# pca10040_sheet4_connectors.net
KiCad netlist of a schematic drawn in Altium Designer
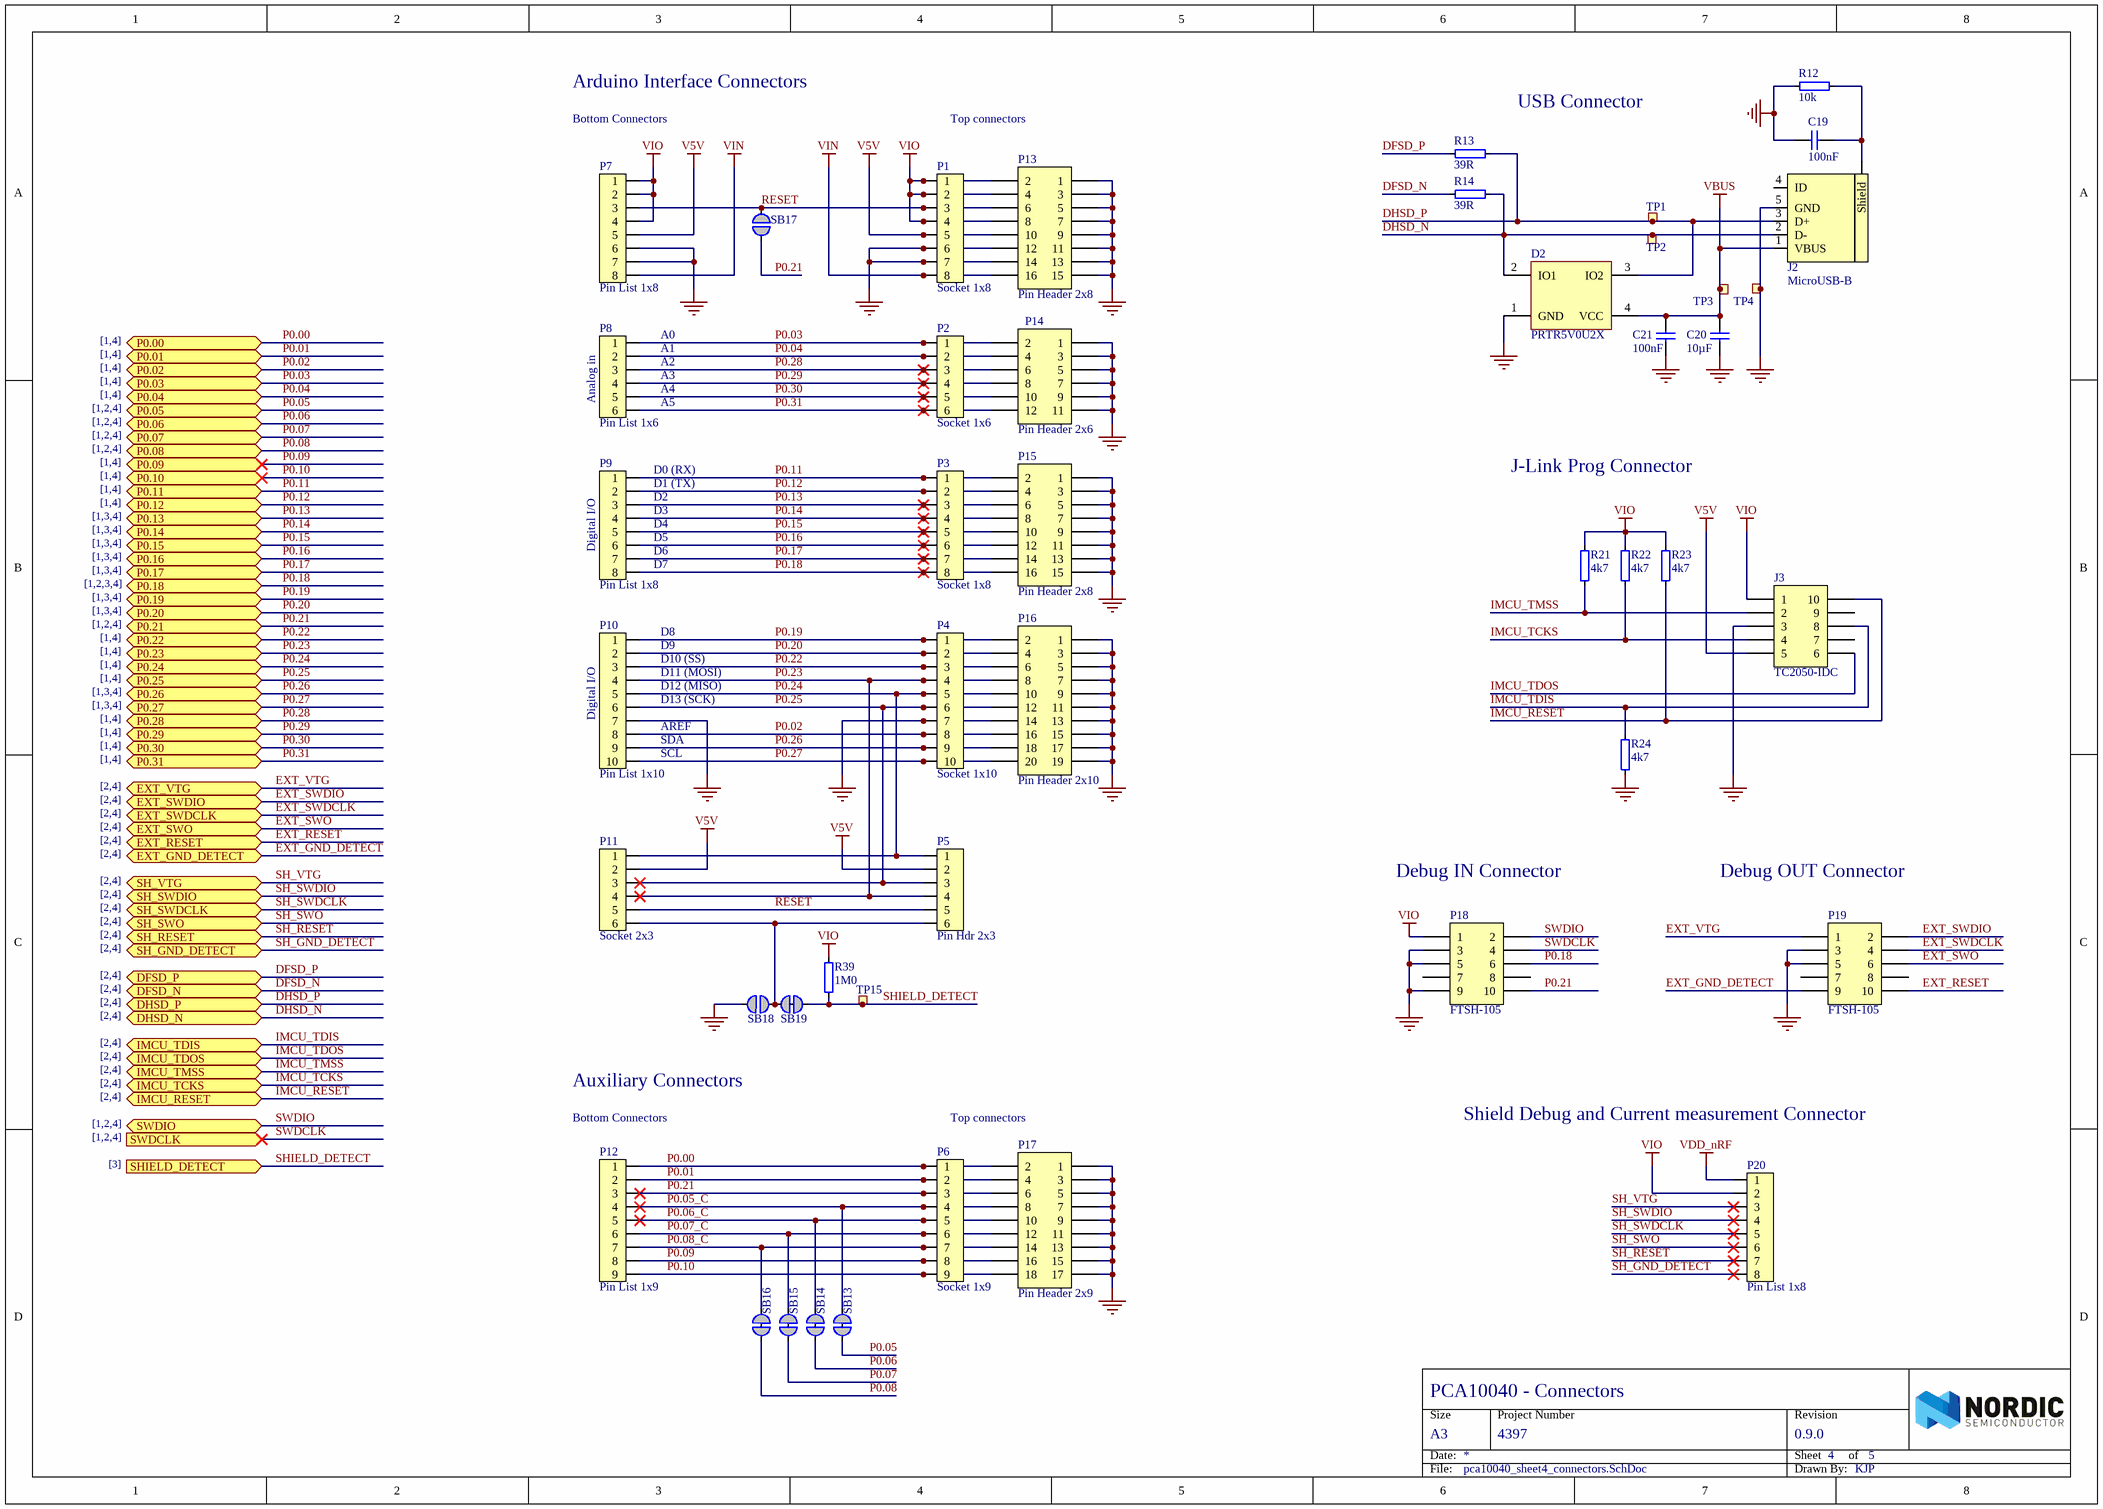
[diagram p0: pca10040_sheet4_connectors.SchDoc]

(export (version "E")
  (design (tool "Eeschema 10.0.6"))
  (components
    (comp (ref "C19")
      (value "100nF")
      (footprint "CAPC1005X04L")
      (description "Capacitor, X7R, ±10%")
      (fields (field (name "PART NUMBER") "C0402-100n") (field (name "PUBLISHER") "Nordic Semiconductor"))
      (libsource (lib "Nordic Passive DB") (part "CAP"))
    )
    (comp (ref "C20")
      (value "10µF")
      (footprint "CAPC1608X06L")
      (description "Capacitor, X5R, ±20%")
      (fields (field (name "PART NUMBER") "C0603-10µ") (field (name "PUBLISHER") "Nordic Semiconductor"))
      (libsource (lib "Nordic Passive DB") (part "CAP"))
    )
    (comp (ref "C21")
      (value "100nF")
      (footprint "CAPC1005X04L")
      (description "Capacitor, X7R, ±10%")
      (fields (field (name "PART NUMBER") "C0402-100n") (field (name "PUBLISHER") "Nordic Semiconductor"))
      (libsource (lib "Nordic Passive DB") (part "CAP"))
    )
    (comp (ref "D2")
      (value "PRTR5V0U2X")
      (footprint "SOT190P230X110-4L")
      (description "Ultra low capacitance double rail-to-rail ESD protection diode")
      (fields
        (field (name "MANUFACTURER") "NXP")
        (field (name "2ND SOURCE PART NUMBER") "152-4157")
        (field (name "PUBLISHER") "Nordic Semiconductor")
      )
      (libsource (lib "Nordic Discrete DB") (part "PRTR5V0U2X"))
    )
    (comp (ref "J2")
      (value "MicroUSB-B")
      (footprint "FCI_10118193-0001LF")
      (description "MicroUSB-B-SMT")
      (fields
        (field (name "PART NUMBER") "FCI 10118193-0001LF")
        (field (name "MANUFACTURER") "FCI")
        (field (name "PUBLISHER") "Nordic Semiconductor")
      )
      (libsource (lib "Nordic Passive DB") (part "MiniUSB-AB-SMT"))
    )
    (comp (ref "J3")
      (value "TC2050-IDC")
      (footprint "TC2050-IDC-NLFP")
      (description "CBL PLUG-OF-NAILS 10-PIN")
      (fields
        (field (name "PART NUMBER") "TC2050-IDC-NLFP")
        (field (name "MANUFACTURER") "Tag-Connect LLC")
        (field (name "PUBLISHER") "Nordic Semiconductor")
      )
      (libsource (lib "Nordic Passive DB") (part "CONN-2x5_var2"))
    )
    (comp (ref "P1")
      (value "Socket 1x8")
      (footprint "SOCKET_1x8_SMD")
      (description "Socket 1x8, 2.54mm (100mil), SMD")
      (fields
        (field (name "PART NUMBER") "Socket 1x8 SMD")
        (field (name "MANUFACTURER") "Samtec")
        (field (name "PUBLISHER") "Nordic Semiconductor")
      )
      (libsource (lib "") (part "CONN-8_1"))
    )
    (comp (ref "P2")
      (value "Socket 1x6")
      (footprint "SOCKET_1x6_SMD")
      (description "Socket 1x6, 2.54mm (100mil), SMD")
      (fields
        (field (name "PART NUMBER") "Socket 1x6 SMD")
        (field (name "MANUFACTURER") "Samtec")
        (field (name "PUBLISHER") "Nordic Semiconductor")
      )
      (libsource (lib "Nordic Passive DB") (part "CONN-6"))
    )
    (comp (ref "P3")
      (value "Socket 1x8")
      (footprint "SOCKET_1x8_SMD")
      (description "Socket 1x8, 2.54mm (100mil), SMD")
      (fields
        (field (name "PART NUMBER") "Socket 1x8 SMD")
        (field (name "MANUFACTURER") "Samtec")
        (field (name "PUBLISHER") "Nordic Semiconductor")
      )
      (libsource (lib "") (part "CONN-8_1"))
    )
    (comp (ref "P4")
      (value "Socket 1x10")
      (footprint "SOCKET_1x10_SMD")
      (description "Socket 1x10, 2.54mm (100mil), SMD")
      (fields
        (field (name "PART NUMBER") "Socket 1x10 SMD")
        (field (name "MANUFACTURER") "Samtec")
        (field (name "PUBLISHER") "Nordic Semiconductor")
      )
      (libsource (lib "Nordic Passive DB") (part "CONN-10"))
    )
    (comp (ref "P5")
      (value "Pin Hdr 2x3")
      (footprint "Molex 15-91-2060")
      (description "Pin Header 2x3, 2.54mm (100mil) SMD")
      (fields
        (field (name "PART NUMBER") "Pin Header 2x3 SMD")
        (field (name "MANUFACTURER") "Molex")
        (field (name "PUBLISHER") "Nordic Semiconductor")
      )
      (libsource (lib "Nordic Passive DB") (part "CONN-6"))
    )
    (comp (ref "P6")
      (value "Socket 1x9")
      (footprint "SOCKET_1x9_SMD")
      (description "Socket 1x9, 2.54mm (100mil), SMD")
      (fields
        (field (name "PART NUMBER") "Socket 1x9 SMD")
        (field (name "MANUFACTURER") "Samtec")
        (field (name "PUBLISHER") "Nordic Semiconductor")
      )
      (libsource (lib "Nordic Passive DB") (part "CONN-9"))
    )
    (comp (ref "P7")
      (value "Pin List 1x8")
      (footprint "LIST_1x8_SMD")
      (description "Pin List 1x8, 2.54mm (100mil), SMD")
      (fields
        (field (name "PART NUMBER") "Pin List 1x8 SMD")
        (field (name "PUBLISHER") "Nordic Semiconductor")
      )
      (libsource (lib "Nordic Passive DB") (part "CONN-8"))
    )
    (comp (ref "P8")
      (value "Pin List 1x6")
      (footprint "LIST_1x6_SMD")
      (description "Pin List 1x6, 2.54mm (100mil), SMD")
      (fields
        (field (name "PART NUMBER") "Pin List 1x6 SMD")
        (field (name "PUBLISHER") "Nordic Semiconductor")
      )
      (libsource (lib "") (part "CONN-6_1"))
    )
    (comp (ref "P9")
      (value "Pin List 1x8")
      (footprint "LIST_1x8_SMD")
      (description "Pin List 1x8, 2.54mm (100mil), SMD")
      (fields
        (field (name "PART NUMBER") "Pin List 1x8 SMD")
        (field (name "PUBLISHER") "Nordic Semiconductor")
      )
      (libsource (lib "Nordic Passive DB") (part "CONN-8"))
    )
    (comp (ref "P10")
      (value "Pin List 1x10")
      (footprint "LIST_1x10_SMD")
      (description "Pin List 1x10, 2.54mm (100mil), SMD")
      (fields
        (field (name "PART NUMBER") "Pin List 1x10 SMD")
        (field (name "PUBLISHER") "Nordic Semiconductor")
      )
      (libsource (lib "") (part "CONN-10_1"))
    )
    (comp (ref "P11")
      (value "Socket 2x3")
      (footprint "SOCKET_2x3_SMD-2.54mm-bottom")
      (description "Socket 2x3, 2.54mm (100mil), SMD")
      (fields
        (field (name "PART NUMBER") "Socket 2x3 SMD Bottom")
        (field (name "MANUFACTURER") "Samtec")
        (field (name "PUBLISHER") "Nordic Semiconductor")
      )
      (libsource (lib "") (part "CONN-6_1"))
    )
    (comp (ref "P12")
      (value "Pin List 1x9")
      (footprint "LIST_1x9_SMD")
      (description "Pin List 1x9, 2.54mm (100mil), SMD")
      (fields
        (field (name "PART NUMBER") "Pin List 1x9 SMD")
        (field (name "PUBLISHER") "Nordic Semiconductor")
      )
      (libsource (lib "") (part "CONN-9_1"))
    )
    (comp (ref "P13")
      (value "Pin Header 2x8")
      (footprint "HDR_2x8")
      (description "Pin Header 2x8, 2.54mm (100mil)")
      (fields (field (name "PUBLISHER") "Nordic Semiconductor"))
      (libsource (lib "Nordic Passive DB") (part "CONN-2x8"))
    )
    (comp (ref "P14")
      (value "Pin Header 2x6")
      (footprint "HDR_2x6")
      (description "Pin Header 2x6, 2.54mm (100mil)")
      (fields (field (name "PUBLISHER") "Nordic Semiconductor"))
      (libsource (lib "Nordic Passive DB") (part "CONN-2x6"))
    )
    (comp (ref "P15")
      (value "Pin Header 2x8")
      (footprint "HDR_2x8")
      (description "Pin Header 2x8, 2.54mm (100mil)")
      (fields (field (name "PUBLISHER") "Nordic Semiconductor"))
      (libsource (lib "Nordic Passive DB") (part "CONN-2x8"))
    )
    (comp (ref "P16")
      (value "Pin Header 2x10")
      (footprint "HDR_2x10")
      (description "Pin Header 2x10, 2.54mm (100mil)")
      (fields (field (name "PUBLISHER") "Nordic Semiconductor"))
      (libsource (lib "Nordic Passive DB") (part "CONN-2x10"))
    )
    (comp (ref "P17")
      (value "Pin Header 2x9")
      (footprint "HDR_2x9")
      (description "Pin Header 2x9, 2.54mm (100mil)")
      (fields (field (name "PUBLISHER") "Nordic Semiconductor"))
      (libsource (lib "Nordic Passive DB") (part "CONN-2x9"))
    )
    (comp (ref "P18")
      (value "FTSH-105")
      (footprint "FTSH-105-K")
      (description "SAMTEC - CONN HEADER 10POS DUAL .05\" SMD KEYING SHROUD")
      (fields
        (field (name "PART NUMBER") "Samtec FTSH-105 Keying Shroud")
        (field (name "MANUFACTURER") "Samtec")
        (field (name "PUBLISHER") "Nordic Semiconductor")
      )
      (libsource (lib "Nordic Passive DB") (part "CONN-2x5"))
    )
    (comp (ref "P19")
      (value "FTSH-105")
      (footprint "FTSH-105-K")
      (description "SAMTEC - CONN HEADER 10POS DUAL .05\" SMD KEYING SHROUD")
      (fields
        (field (name "PART NUMBER") "Samtec FTSH-105 Keying Shroud")
        (field (name "MANUFACTURER") "Samtec")
        (field (name "PUBLISHER") "Nordic Semiconductor")
      )
      (libsource (lib "Nordic Passive DB") (part "CONN-2x5"))
    )
    (comp (ref "P20")
      (value "Pin List 1x8")
      (footprint "LIST_1x8_SMD")
      (description "Pin List 1x8, 2.54mm (100mil), SMD")
      (fields
        (field (name "PART NUMBER") "Pin List 1x8 SMD")
        (field (name "PUBLISHER") "Nordic Semiconductor")
      )
      (libsource (lib "") (part "CONN-8_1"))
    )
    (comp (ref "R12")
      (value "10k")
      (footprint "RESC1005X04L")
      (description "Resistor, ±1%, 0.063W")
      (fields (field (name "PART NUMBER") "R0402-10k") (field (name "PUBLISHER") "Nordic Semiconductor"))
      (libsource (lib "Nordic Passive DB") (part "RES_1"))
    )
    (comp (ref "R13")
      (value "39R")
      (footprint "RESC1005X04L")
      (description "Resistor, ±1%, 0.063W")
      (fields (field (name "PART NUMBER") "R0402-39R") (field (name "PUBLISHER") "Nordic Semiconductor"))
      (libsource (lib "Nordic Passive DB") (part "RES_1"))
    )
    (comp (ref "R14")
      (value "39R")
      (footprint "RESC1005X04L")
      (description "Resistor, ±1%, 0.063W")
      (fields (field (name "PART NUMBER") "R0402-39R") (field (name "PUBLISHER") "Nordic Semiconductor"))
      (libsource (lib "Nordic Passive DB") (part "RES_1"))
    )
    (comp (ref "R21")
      (value "4k7")
      (footprint "RESC1005X04L")
      (description "Resistor, ±1%, 0.063W")
      (fields (field (name "PART NUMBER") "R0402-4k7") (field (name "PUBLISHER") "Nordic Semiconductor"))
      (libsource (lib "Nordic Passive DB") (part "RES_1"))
    )
    (comp (ref "R22")
      (value "4k7")
      (footprint "RESC1005X04L")
      (description "Resistor, ±1%, 0.063W")
      (fields (field (name "PART NUMBER") "R0402-4k7") (field (name "PUBLISHER") "Nordic Semiconductor"))
      (libsource (lib "Nordic Passive DB") (part "RES_1"))
    )
    (comp (ref "R23")
      (value "4k7")
      (footprint "RESC1005X04L")
      (description "Resistor, ±1%, 0.063W")
      (fields (field (name "PART NUMBER") "R0402-4k7") (field (name "PUBLISHER") "Nordic Semiconductor"))
      (libsource (lib "Nordic Passive DB") (part "RES_1"))
    )
    (comp (ref "R24")
      (value "4k7")
      (footprint "RESC1005X04L")
      (description "Resistor, ±1%, 0.063W")
      (fields (field (name "PART NUMBER") "R0402-4k7") (field (name "PUBLISHER") "Nordic Semiconductor"))
      (libsource (lib "Nordic Passive DB") (part "RES_1"))
    )
    (comp (ref "R39")
      (value "1M0")
      (footprint "RESC1005X04L")
      (description "Resistor, ±1%, 0.063W")
      (fields (field (name "PART NUMBER") "R0402-1M0") (field (name "PUBLISHER") "Nordic Semiconductor"))
      (libsource (lib "Nordic Passive DB") (part "RES_1"))
    )
    (comp (ref "SB13")
      (value "Solderbridge")
      (footprint "Solderbridge_Shorted")
      (description "Shorted Solderbridge")
      (fields
        (field (name "PART NUMBER") "Solderbridge Shorted")
        (field (name "PUBLISHER") "Nordic Semiconductor")
      )
      (libsource (lib "Nordic Passive DB") (part "SOLDERBRIDGE_SHORTED"))
    )
    (comp (ref "SB14")
      (value "Solderbridge")
      (footprint "Solderbridge_Shorted")
      (description "Shorted Solderbridge")
      (fields
        (field (name "PART NUMBER") "Solderbridge Shorted")
        (field (name "PUBLISHER") "Nordic Semiconductor")
      )
      (libsource (lib "Nordic Passive DB") (part "SOLDERBRIDGE_SHORTED"))
    )
    (comp (ref "SB15")
      (value "Solderbridge")
      (footprint "Solderbridge_Shorted")
      (description "Shorted Solderbridge")
      (fields
        (field (name "PART NUMBER") "Solderbridge Shorted")
        (field (name "PUBLISHER") "Nordic Semiconductor")
      )
      (libsource (lib "Nordic Passive DB") (part "SOLDERBRIDGE_SHORTED"))
    )
    (comp (ref "SB16")
      (value "Solderbridge")
      (footprint "Solderbridge_Shorted")
      (description "Shorted Solderbridge")
      (fields
        (field (name "PART NUMBER") "Solderbridge Shorted")
        (field (name "PUBLISHER") "Nordic Semiconductor")
      )
      (libsource (lib "Nordic Passive DB") (part "SOLDERBRIDGE_SHORTED"))
    )
    (comp (ref "SB17")
      (value "Solderbridge")
      (footprint "Solderbridge")
      (fields (field (name "PUBLISHER") "Nordic Semiconductor"))
      (libsource (lib "Nordic Passive DB") (part "SOLDERBRIDGE"))
    )
    (comp (ref "SB18")
      (value "Solderbridge")
      (footprint "Solderbridge")
      (fields (field (name "PUBLISHER") "Nordic Semiconductor"))
      (libsource (lib "Nordic Passive DB") (part "SOLDERBRIDGE"))
    )
    (comp (ref "SB19")
      (value "Solderbridge")
      (footprint "Solderbridge_Shorted")
      (description "Shorted Solderbridge")
      (fields
        (field (name "PART NUMBER") "Solderbridge Shorted")
        (field (name "PUBLISHER") "Nordic Semiconductor")
      )
      (libsource (lib "Nordic Passive DB") (part "SOLDERBRIDGE_SHORTED"))
    )
    (comp (ref "TP1")
      (value "Ø1.0mm,SMD")
      (footprint "TP_SMD_Ø1.0mm")
      (description "1.0mm circular SMD testpad")
      (fields
        (field (name "PART NUMBER") "TP_SMD_Ø1.0MM")
        (field (name "MANUFACTURER") "Nordic Semiconductor")
        (field (name "PUBLISHER") "Nordic Semiconductor")
      )
      (libsource (lib "") (part "TESTPAD_1"))
    )
    (comp (ref "TP2")
      (value "Ø1.0mm,SMD")
      (footprint "TP_SMD_Ø1.0mm")
      (description "1.0mm circular SMD testpad")
      (fields
        (field (name "PART NUMBER") "TP_SMD_Ø1.0MM")
        (field (name "MANUFACTURER") "Nordic Semiconductor")
        (field (name "PUBLISHER") "Nordic Semiconductor")
      )
      (libsource (lib "Nordic Passive DB") (part "TESTPAD"))
    )
    (comp (ref "TP3")
      (value "Ø1.0mm,SMD")
      (footprint "TP_SMD_Ø1.0mm")
      (description "1.0mm circular SMD testpad")
      (fields
        (field (name "PART NUMBER") "TP_SMD_Ø1.0MM")
        (field (name "MANUFACTURER") "Nordic Semiconductor")
        (field (name "PUBLISHER") "Nordic Semiconductor")
      )
      (libsource (lib "") (part "TESTPAD_3"))
    )
    (comp (ref "TP4")
      (value "Ø1.0mm,SMD")
      (footprint "TP_SMD_Ø1.0mm")
      (description "1.0mm circular SMD testpad")
      (fields
        (field (name "PART NUMBER") "TP_SMD_Ø1.0MM")
        (field (name "MANUFACTURER") "Nordic Semiconductor")
        (field (name "PUBLISHER") "Nordic Semiconductor")
      )
      (libsource (lib "") (part "TESTPAD_2"))
    )
    (comp (ref "TP15")
      (value "Ø1.0mm,SMD")
      (footprint "TP_SMD_Ø1.0mm")
      (description "1.0mm circular SMD testpad")
      (fields
        (field (name "PART NUMBER") "TP_SMD_Ø1.0MM")
        (field (name "MANUFACTURER") "Nordic Semiconductor")
        (field (name "PUBLISHER") "Nordic Semiconductor")
      )
      (libsource (lib "") (part "TESTPAD_1"))
    )
  )
  (nets
    (net (code "1") (name "/DFSD_N") (class "Default")
      (node (ref "R14") (pin "1") (pinfunction "1_1") (pintype "passive"))
    )
    (net (code "2") (name "/DFSD_P") (class "Default")
      (node (ref "R13") (pin "1") (pinfunction "1_1") (pintype "passive"))
    )
    (net (code "3") (name "/DHSD_N") (class "Default")
      (node (ref "D2") (pin "2") (pinfunction "IO1_2") (pintype "passive"))
      (node (ref "J2") (pin "2") (pinfunction "D-_2") (pintype "passive"))
      (node (ref "R14") (pin "2") (pinfunction "2_2") (pintype "passive"))
      (node (ref "TP2") (pin "1") (pinfunction "1_1") (pintype "passive"))
    )
    (net (code "4") (name "/DHSD_P") (class "Default")
      (node (ref "D2") (pin "3") (pinfunction "IO2_3") (pintype "passive"))
      (node (ref "J2") (pin "3") (pinfunction "D+_3") (pintype "passive"))
      (node (ref "R13") (pin "2") (pinfunction "2_2") (pintype "passive"))
      (node (ref "TP1") (pin "1") (pinfunction "1_1") (pintype "passive"))
    )
    (net (code "5") (name "/EXT_GND_DETECT") (class "Default")
      (node (ref "P19") (pin "9") (pinfunction "9_9") (pintype "passive"))
    )
    (net (code "6") (name "/EXT_RESET") (class "Default")
      (node (ref "P19") (pin "10") (pinfunction "10_10") (pintype "passive"))
    )
    (net (code "7") (name "/EXT_SWDCLK") (class "Default")
      (node (ref "P19") (pin "4") (pinfunction "4_4") (pintype "passive"))
    )
    (net (code "8") (name "/EXT_SWDIO") (class "Default")
      (node (ref "P19") (pin "2") (pinfunction "2_2") (pintype "passive"))
    )
    (net (code "9") (name "/EXT_SWO") (class "Default")
      (node (ref "P19") (pin "6") (pinfunction "6_6") (pintype "passive"))
    )
    (net (code "10") (name "/EXT_VTG") (class "Default")
      (node (ref "P19") (pin "1") (pinfunction "1_1") (pintype "passive"))
    )
    (net (code "11") (name "/IMCU_RESET") (class "Default")
      (node (ref "J3") (pin "10") (pinfunction "10_10") (pintype "passive"))
      (node (ref "R23") (pin "1") (pinfunction "1_1") (pintype "passive"))
    )
    (net (code "12") (name "/IMCU_TCKS") (class "Default")
      (node (ref "J3") (pin "4") (pinfunction "4_4") (pintype "passive"))
      (node (ref "R22") (pin "1") (pinfunction "1_1") (pintype "passive"))
    )
    (net (code "13") (name "/IMCU_TDIS") (class "Default")
      (node (ref "J3") (pin "8") (pinfunction "8_8") (pintype "passive"))
      (node (ref "R24") (pin "1") (pinfunction "1_1") (pintype "passive"))
    )
    (net (code "14") (name "/IMCU_TDOS") (class "Default")
      (node (ref "J3") (pin "6") (pinfunction "6_6") (pintype "passive"))
    )
    (net (code "15") (name "/IMCU_TMSS") (class "Default")
      (node (ref "J3") (pin "2") (pinfunction "2_2") (pintype "passive"))
      (node (ref "R21") (pin "1") (pinfunction "1_1") (pintype "passive"))
    )
    (net (code "16") (name "/P0.00") (class "Default")
      (node (ref "P12") (pin "1") (pinfunction "1_1") (pintype "passive"))
      (node (ref "P17") (pin "2") (pinfunction "2_2") (pintype "passive"))
      (node (ref "P6") (pin "1") (pinfunction "1_1") (pintype "passive"))
    )
    (net (code "17") (name "/P0.01") (class "Default")
      (node (ref "P12") (pin "2") (pinfunction "2_2") (pintype "passive"))
      (node (ref "P17") (pin "4") (pinfunction "4_4") (pintype "passive"))
      (node (ref "P6") (pin "2") (pinfunction "2_2") (pintype "passive"))
    )
    (net (code "18") (name "/P0.02") (class "Default")
      (node (ref "P10") (pin "8") (pinfunction "8_8") (pintype "passive"))
      (node (ref "P16") (pin "16") (pinfunction "16_16") (pintype "passive"))
      (node (ref "P4") (pin "8") (pinfunction "8_8") (pintype "passive"))
    )
    (net (code "19") (name "/P0.03") (class "Default")
      (node (ref "P14") (pin "2") (pinfunction "2_2") (pintype "passive"))
      (node (ref "P2") (pin "1") (pinfunction "1_1") (pintype "passive"))
      (node (ref "P8") (pin "1") (pinfunction "1_1") (pintype "passive"))
    )
    (net (code "20") (name "/P0.04") (class "Default")
      (node (ref "P14") (pin "4") (pinfunction "4_4") (pintype "passive"))
      (node (ref "P2") (pin "2") (pinfunction "2_2") (pintype "passive"))
      (node (ref "P8") (pin "2") (pinfunction "2_2") (pintype "passive"))
    )
    (net (code "21") (name "/P0.05") (class "Default")
      (node (ref "SB13") (pin "2") (pinfunction "1_2") (pintype "passive"))
    )
    (net (code "22") (name "/P0.05_C") (class "Default")
      (node (ref "P12") (pin "4") (pinfunction "4_4") (pintype "power_in"))
      (node (ref "P17") (pin "8") (pinfunction "8_8") (pintype "passive"))
      (node (ref "P6") (pin "4") (pinfunction "4_4") (pintype "power_in"))
      (node (ref "SB13") (pin "1") (pinfunction "0_1") (pintype "passive"))
    )
    (net (code "23") (name "/P0.06") (class "Default")
      (node (ref "SB14") (pin "2") (pinfunction "1_2") (pintype "passive"))
    )
    (net (code "24") (name "/P0.06_C") (class "Default")
      (node (ref "P12") (pin "5") (pinfunction "5_5") (pintype "power_in"))
      (node (ref "P17") (pin "10") (pinfunction "10_10") (pintype "passive"))
      (node (ref "P6") (pin "5") (pinfunction "5_5") (pintype "power_in"))
      (node (ref "SB14") (pin "1") (pinfunction "0_1") (pintype "passive"))
    )
    (net (code "25") (name "/P0.07") (class "Default")
      (node (ref "SB15") (pin "2") (pinfunction "1_2") (pintype "passive"))
    )
    (net (code "26") (name "/P0.07_C") (class "Default")
      (node (ref "P12") (pin "6") (pinfunction "6_6") (pintype "power_in"))
      (node (ref "P17") (pin "12") (pinfunction "12_12") (pintype "passive"))
      (node (ref "P6") (pin "6") (pinfunction "6_6") (pintype "power_in"))
      (node (ref "SB15") (pin "1") (pinfunction "0_1") (pintype "passive"))
    )
    (net (code "27") (name "/P0.08") (class "Default")
      (node (ref "SB16") (pin "2") (pinfunction "1_2") (pintype "passive"))
    )
    (net (code "28") (name "/P0.08_C") (class "Default")
      (node (ref "P12") (pin "7") (pinfunction "7_7") (pintype "power_in"))
      (node (ref "P17") (pin "14") (pinfunction "14_14") (pintype "passive"))
      (node (ref "P6") (pin "7") (pinfunction "7_7") (pintype "power_in"))
      (node (ref "SB16") (pin "1") (pinfunction "0_1") (pintype "passive"))
    )
    (net (code "29") (name "/P0.09") (class "Default")
      (node (ref "P12") (pin "8") (pinfunction "8_8") (pintype "power_in"))
      (node (ref "P17") (pin "16") (pinfunction "16_16") (pintype "passive"))
      (node (ref "P6") (pin "8") (pinfunction "8_8") (pintype "power_in"))
    )
    (net (code "30") (name "/P0.10") (class "Default")
      (node (ref "P12") (pin "9") (pinfunction "9_9") (pintype "power_in"))
      (node (ref "P17") (pin "18") (pinfunction "18_18") (pintype "passive"))
      (node (ref "P6") (pin "9") (pinfunction "9_9") (pintype "power_in"))
    )
    (net (code "31") (name "/P0.11") (class "Default")
      (node (ref "P15") (pin "2") (pinfunction "2_2") (pintype "passive"))
      (node (ref "P3") (pin "1") (pinfunction "1_1") (pintype "passive"))
      (node (ref "P9") (pin "1") (pinfunction "1_1") (pintype "passive"))
    )
    (net (code "32") (name "/P0.12") (class "Default")
      (node (ref "P15") (pin "4") (pinfunction "4_4") (pintype "passive"))
      (node (ref "P3") (pin "2") (pinfunction "2_2") (pintype "passive"))
      (node (ref "P9") (pin "2") (pinfunction "2_2") (pintype "passive"))
    )
    (net (code "33") (name "/P0.13") (class "Default")
      (node (ref "P15") (pin "6") (pinfunction "6_6") (pintype "passive"))
      (node (ref "P3") (pin "3") (pinfunction "3_3") (pintype "power_in"))
      (node (ref "P9") (pin "3") (pinfunction "3_3") (pintype "power_in"))
    )
    (net (code "34") (name "/P0.14") (class "Default")
      (node (ref "P15") (pin "8") (pinfunction "8_8") (pintype "passive"))
      (node (ref "P3") (pin "4") (pinfunction "4_4") (pintype "power_in"))
      (node (ref "P9") (pin "4") (pinfunction "4_4") (pintype "power_in"))
    )
    (net (code "35") (name "/P0.15") (class "Default")
      (node (ref "P15") (pin "10") (pinfunction "10_10") (pintype "passive"))
      (node (ref "P3") (pin "5") (pinfunction "5_5") (pintype "power_in"))
      (node (ref "P9") (pin "5") (pinfunction "5_5") (pintype "power_in"))
    )
    (net (code "36") (name "/P0.16") (class "Default")
      (node (ref "P15") (pin "12") (pinfunction "12_12") (pintype "passive"))
      (node (ref "P3") (pin "6") (pinfunction "6_6") (pintype "power_in"))
      (node (ref "P9") (pin "6") (pinfunction "6_6") (pintype "power_in"))
    )
    (net (code "37") (name "/P0.17") (class "Default")
      (node (ref "P15") (pin "14") (pinfunction "14_14") (pintype "passive"))
      (node (ref "P3") (pin "7") (pinfunction "7_7") (pintype "power_in"))
      (node (ref "P9") (pin "7") (pinfunction "7_7") (pintype "power_in"))
    )
    (net (code "38") (name "/P0.18") (class "Default")
      (node (ref "P15") (pin "16") (pinfunction "16_16") (pintype "passive"))
      (node (ref "P18") (pin "6") (pinfunction "6_6") (pintype "passive"))
      (node (ref "P3") (pin "8") (pinfunction "8_8") (pintype "power_in"))
      (node (ref "P9") (pin "8") (pinfunction "8_8") (pintype "power_in"))
    )
    (net (code "39") (name "/P0.19") (class "Default")
      (node (ref "P10") (pin "1") (pinfunction "1_1") (pintype "passive"))
      (node (ref "P16") (pin "2") (pinfunction "2_2") (pintype "passive"))
      (node (ref "P4") (pin "1") (pinfunction "1_1") (pintype "passive"))
    )
    (net (code "40") (name "/P0.20") (class "Default")
      (node (ref "P10") (pin "2") (pinfunction "2_2") (pintype "passive"))
      (node (ref "P16") (pin "4") (pinfunction "4_4") (pintype "passive"))
      (node (ref "P4") (pin "2") (pinfunction "2_2") (pintype "passive"))
    )
    (net (code "41") (name "/P0.21") (class "Default")
      (node (ref "P12") (pin "3") (pinfunction "3_3") (pintype "power_in"))
      (node (ref "P17") (pin "6") (pinfunction "6_6") (pintype "passive"))
      (node (ref "P18") (pin "10") (pinfunction "10_10") (pintype "passive"))
      (node (ref "P6") (pin "3") (pinfunction "3_3") (pintype "power_in"))
      (node (ref "SB17") (pin "2") (pinfunction "1_2") (pintype "passive"))
    )
    (net (code "42") (name "/P0.22") (class "Default")
      (node (ref "P10") (pin "3") (pinfunction "3_3") (pintype "passive"))
      (node (ref "P16") (pin "6") (pinfunction "6_6") (pintype "passive"))
      (node (ref "P4") (pin "3") (pinfunction "3_3") (pintype "passive"))
    )
    (net (code "43") (name "/P0.23") (class "Default")
      (node (ref "P10") (pin "4") (pinfunction "4_4") (pintype "passive"))
      (node (ref "P11") (pin "4") (pinfunction "4_4") (pintype "power_in"))
      (node (ref "P16") (pin "8") (pinfunction "8_8") (pintype "passive"))
      (node (ref "P4") (pin "4") (pinfunction "4_4") (pintype "passive"))
      (node (ref "P5") (pin "4") (pinfunction "4_4") (pintype "power_in"))
    )
    (net (code "44") (name "/P0.24") (class "Default")
      (node (ref "P10") (pin "5") (pinfunction "5_5") (pintype "passive"))
      (node (ref "P11") (pin "1") (pinfunction "1_1") (pintype "passive"))
      (node (ref "P16") (pin "10") (pinfunction "10_10") (pintype "passive"))
      (node (ref "P4") (pin "5") (pinfunction "5_5") (pintype "passive"))
      (node (ref "P5") (pin "1") (pinfunction "1_1") (pintype "passive"))
    )
    (net (code "45") (name "/P0.25") (class "Default")
      (node (ref "P10") (pin "6") (pinfunction "6_6") (pintype "passive"))
      (node (ref "P11") (pin "3") (pinfunction "3_3") (pintype "power_in"))
      (node (ref "P16") (pin "12") (pinfunction "12_12") (pintype "passive"))
      (node (ref "P4") (pin "6") (pinfunction "6_6") (pintype "passive"))
      (node (ref "P5") (pin "3") (pinfunction "3_3") (pintype "power_in"))
    )
    (net (code "46") (name "/P0.26") (class "Default")
      (node (ref "P10") (pin "9") (pinfunction "9_9") (pintype "passive"))
      (node (ref "P16") (pin "18") (pinfunction "18_18") (pintype "passive"))
      (node (ref "P4") (pin "9") (pinfunction "9_9") (pintype "passive"))
    )
    (net (code "47") (name "/P0.27") (class "Default")
      (node (ref "P10") (pin "10") (pinfunction "10_10") (pintype "passive"))
      (node (ref "P16") (pin "20") (pinfunction "20_20") (pintype "passive"))
      (node (ref "P4") (pin "10") (pinfunction "10_10") (pintype "passive"))
    )
    (net (code "48") (name "/P0.28") (class "Default")
      (node (ref "P14") (pin "6") (pinfunction "6_6") (pintype "passive"))
      (node (ref "P2") (pin "3") (pinfunction "3_3") (pintype "power_in"))
      (node (ref "P8") (pin "3") (pinfunction "3_3") (pintype "power_in"))
    )
    (net (code "49") (name "/P0.29") (class "Default")
      (node (ref "P14") (pin "8") (pinfunction "8_8") (pintype "passive"))
      (node (ref "P2") (pin "4") (pinfunction "4_4") (pintype "power_in"))
      (node (ref "P8") (pin "4") (pinfunction "4_4") (pintype "power_in"))
    )
    (net (code "50") (name "/P0.30") (class "Default")
      (node (ref "P14") (pin "10") (pinfunction "10_10") (pintype "passive"))
      (node (ref "P2") (pin "5") (pinfunction "5_5") (pintype "power_in"))
      (node (ref "P8") (pin "5") (pinfunction "5_5") (pintype "power_in"))
    )
    (net (code "51") (name "/P0.31") (class "Default")
      (node (ref "P14") (pin "12") (pinfunction "12_12") (pintype "passive"))
      (node (ref "P2") (pin "6") (pinfunction "6_6") (pintype "power_in"))
      (node (ref "P8") (pin "6") (pinfunction "6_6") (pintype "power_in"))
    )
    (net (code "52") (name "/RESET") (class "Default")
      (node (ref "P1") (pin "3") (pinfunction "3_3") (pintype "power_in"))
      (node (ref "P11") (pin "5") (pinfunction "5_5") (pintype "power_in"))
      (node (ref "P13") (pin "6") (pinfunction "6_6") (pintype "passive"))
      (node (ref "P5") (pin "5") (pinfunction "5_5") (pintype "power_in"))
      (node (ref "P7") (pin "3") (pinfunction "3_3") (pintype "power_in"))
      (node (ref "SB17") (pin "1") (pinfunction "0_1") (pintype "passive"))
    )
    (net (code "53") (name "/SHIELD_DETECT") (class "Default")
      (node (ref "R39") (pin "1") (pinfunction "1_1") (pintype "passive"))
      (node (ref "SB19") (pin "2") (pinfunction "1_2") (pintype "passive"))
      (node (ref "TP15") (pin "1") (pinfunction "1_1") (pintype "passive"))
    )
    (net (code "54") (name "/SH_GND_DETECT") (class "Default")
      (node (ref "P20") (pin "8") (pinfunction "8_8") (pintype "power_in+no_connect"))
    )
    (net (code "55") (name "/SH_RESET") (class "Default")
      (node (ref "P20") (pin "7") (pinfunction "7_7") (pintype "power_in+no_connect"))
    )
    (net (code "56") (name "/SH_SWDCLK") (class "Default")
      (node (ref "P20") (pin "5") (pinfunction "5_5") (pintype "power_in+no_connect"))
    )
    (net (code "57") (name "/SH_SWDIO") (class "Default")
      (node (ref "P20") (pin "4") (pinfunction "4_4") (pintype "power_in+no_connect"))
    )
    (net (code "58") (name "/SH_SWO") (class "Default")
      (node (ref "P20") (pin "6") (pinfunction "6_6") (pintype "power_in+no_connect"))
    )
    (net (code "59") (name "/SH_VTG") (class "Default")
      (node (ref "P20") (pin "3") (pinfunction "3_3") (pintype "power_in+no_connect"))
    )
    (net (code "60") (name "/SWDCLK") (class "Default")
      (node (ref "P18") (pin "4") (pinfunction "4_4") (pintype "passive"))
    )
    (net (code "61") (name "/SWDIO") (class "Default")
      (node (ref "P18") (pin "2") (pinfunction "2_2") (pintype "passive"))
    )
    (net (code "62") (name "GND") (class "Default")
      (node (ref "C19") (pin "1") (pinfunction "1_1") (pintype "passive"))
      (node (ref "C20") (pin "1") (pinfunction "1_1") (pintype "passive"))
      (node (ref "C21") (pin "1") (pinfunction "1_1") (pintype "passive"))
      (node (ref "D2") (pin "1") (pinfunction "GND_1") (pintype "passive"))
      (node (ref "J2") (pin "5") (pinfunction "GND_5") (pintype "power_in"))
      (node (ref "J3") (pin "3") (pinfunction "3_3") (pintype "passive"))
      (node (ref "P1") (pin "6") (pinfunction "6_6") (pintype "power_in"))
      (node (ref "P1") (pin "7") (pinfunction "7_7") (pintype "power_in"))
      (node (ref "P10") (pin "7") (pinfunction "7_7") (pintype "passive"))
      (node (ref "P13") (pin "1") (pinfunction "1_1") (pintype "passive"))
      (node (ref "P13") (pin "11") (pinfunction "11_11") (pintype "passive"))
      (node (ref "P13") (pin "12") (pinfunction "12_12") (pintype "passive"))
      (node (ref "P13") (pin "13") (pinfunction "13_13") (pintype "passive"))
      (node (ref "P13") (pin "14") (pinfunction "14_14") (pintype "passive"))
      (node (ref "P13") (pin "15") (pinfunction "15_15") (pintype "passive"))
      (node (ref "P13") (pin "3") (pinfunction "3_3") (pintype "passive"))
      (node (ref "P13") (pin "5") (pinfunction "5_5") (pintype "passive"))
      (node (ref "P13") (pin "7") (pinfunction "7_7") (pintype "passive"))
      (node (ref "P13") (pin "9") (pinfunction "9_9") (pintype "passive"))
      (node (ref "P14") (pin "1") (pinfunction "1_1") (pintype "passive"))
      (node (ref "P14") (pin "11") (pinfunction "11_11") (pintype "passive"))
      (node (ref "P14") (pin "3") (pinfunction "3_3") (pintype "passive"))
      (node (ref "P14") (pin "5") (pinfunction "5_5") (pintype "passive"))
      (node (ref "P14") (pin "7") (pinfunction "7_7") (pintype "passive"))
      (node (ref "P14") (pin "9") (pinfunction "9_9") (pintype "passive"))
      (node (ref "P15") (pin "1") (pinfunction "1_1") (pintype "passive"))
      (node (ref "P15") (pin "11") (pinfunction "11_11") (pintype "passive"))
      (node (ref "P15") (pin "13") (pinfunction "13_13") (pintype "passive"))
      (node (ref "P15") (pin "15") (pinfunction "15_15") (pintype "passive"))
      (node (ref "P15") (pin "3") (pinfunction "3_3") (pintype "passive"))
      (node (ref "P15") (pin "5") (pinfunction "5_5") (pintype "passive"))
      (node (ref "P15") (pin "7") (pinfunction "7_7") (pintype "passive"))
      (node (ref "P15") (pin "9") (pinfunction "9_9") (pintype "passive"))
      (node (ref "P16") (pin "1") (pinfunction "1_1") (pintype "passive"))
      (node (ref "P16") (pin "11") (pinfunction "11_11") (pintype "passive"))
      (node (ref "P16") (pin "13") (pinfunction "13_13") (pintype "passive"))
      (node (ref "P16") (pin "14") (pinfunction "14_14") (pintype "passive"))
      (node (ref "P16") (pin "15") (pinfunction "15_15") (pintype "passive"))
      (node (ref "P16") (pin "17") (pinfunction "17_17") (pintype "passive"))
      (node (ref "P16") (pin "19") (pinfunction "19_19") (pintype "passive"))
      (node (ref "P16") (pin "3") (pinfunction "3_3") (pintype "passive"))
      (node (ref "P16") (pin "5") (pinfunction "5_5") (pintype "passive"))
      (node (ref "P16") (pin "7") (pinfunction "7_7") (pintype "passive"))
      (node (ref "P16") (pin "9") (pinfunction "9_9") (pintype "passive"))
      (node (ref "P17") (pin "1") (pinfunction "1_1") (pintype "passive"))
      (node (ref "P17") (pin "11") (pinfunction "11_11") (pintype "passive"))
      (node (ref "P17") (pin "13") (pinfunction "13_13") (pintype "passive"))
      (node (ref "P17") (pin "15") (pinfunction "15_15") (pintype "passive"))
      (node (ref "P17") (pin "17") (pinfunction "17_17") (pintype "passive"))
      (node (ref "P17") (pin "3") (pinfunction "3_3") (pintype "passive"))
      (node (ref "P17") (pin "5") (pinfunction "5_5") (pintype "passive"))
      (node (ref "P17") (pin "7") (pinfunction "7_7") (pintype "passive"))
      (node (ref "P17") (pin "9") (pinfunction "9_9") (pintype "passive"))
      (node (ref "P18") (pin "3") (pinfunction "3_3") (pintype "passive"))
      (node (ref "P18") (pin "5") (pinfunction "5_5") (pintype "passive"))
      (node (ref "P18") (pin "9") (pinfunction "9_9") (pintype "passive"))
      (node (ref "P19") (pin "3") (pinfunction "3_3") (pintype "passive"))
      (node (ref "P19") (pin "5") (pinfunction "5_5") (pintype "passive"))
      (node (ref "P4") (pin "7") (pinfunction "7_7") (pintype "passive"))
      (node (ref "P7") (pin "6") (pinfunction "6_6") (pintype "power_in"))
      (node (ref "P7") (pin "7") (pinfunction "7_7") (pintype "power_in"))
      (node (ref "R12") (pin "1") (pinfunction "1_1") (pintype "passive"))
      (node (ref "R24") (pin "2") (pinfunction "2_2") (pintype "passive"))
      (node (ref "SB18") (pin "1") (pinfunction "0_1") (pintype "passive"))
      (node (ref "TP4") (pin "1") (pinfunction "1_1") (pintype "passive"))
    )
    (net (code "63") (name "Net-(J2-Shield)") (class "Default")
      (node (ref "C19") (pin "2") (pinfunction "2_2") (pintype "passive"))
      (node (ref "J2") (pin "6") (pinfunction "Shield_6") (pintype "power_in"))
      (node (ref "R12") (pin "2") (pinfunction "2_2") (pintype "passive"))
    )
    (net (code "64") (name "Net-(SB18-1)") (class "Default")
      (node (ref "P11") (pin "6") (pinfunction "6_6") (pintype "power_in"))
      (node (ref "P5") (pin "6") (pinfunction "6_6") (pintype "power_in"))
      (node (ref "SB18") (pin "2") (pinfunction "1_2") (pintype "passive"))
      (node (ref "SB19") (pin "1") (pinfunction "0_1") (pintype "passive"))
    )
    (net (code "65") (name "V5V") (class "Default")
      (node (ref "J3") (pin "5") (pinfunction "5_5") (pintype "passive"))
      (node (ref "P1") (pin "5") (pinfunction "5_5") (pintype "power_in"))
      (node (ref "P11") (pin "2") (pinfunction "2_2") (pintype "passive"))
      (node (ref "P13") (pin "10") (pinfunction "10_10") (pintype "passive"))
      (node (ref "P5") (pin "2") (pinfunction "2_2") (pintype "passive"))
      (node (ref "P7") (pin "5") (pinfunction "5_5") (pintype "power_in"))
    )
    (net (code "66") (name "VBUS") (class "Default")
      (node (ref "C20") (pin "2") (pinfunction "2_2") (pintype "passive"))
      (node (ref "C21") (pin "2") (pinfunction "2_2") (pintype "passive"))
      (node (ref "D2") (pin "4") (pinfunction "VCC_4") (pintype "passive"))
      (node (ref "J2") (pin "1") (pinfunction "VBUS_1") (pintype "power_in"))
      (node (ref "TP3") (pin "1") (pinfunction "1_1") (pintype "passive"))
    )
    (net (code "67") (name "VDD_nRF") (class "Default")
      (node (ref "P20") (pin "1") (pinfunction "1_1") (pintype "passive"))
    )
    (net (code "68") (name "VIN") (class "Default")
      (node (ref "P1") (pin "8") (pinfunction "8_8") (pintype "power_in"))
      (node (ref "P13") (pin "16") (pinfunction "16_16") (pintype "passive"))
      (node (ref "P7") (pin "8") (pinfunction "8_8") (pintype "power_in"))
    )
    (net (code "69") (name "VIO") (class "Default")
      (node (ref "J3") (pin "1") (pinfunction "1_1") (pintype "passive"))
      (node (ref "P1") (pin "1") (pinfunction "1_1") (pintype "passive"))
      (node (ref "P1") (pin "2") (pinfunction "2_2") (pintype "passive"))
      (node (ref "P1") (pin "4") (pinfunction "4_4") (pintype "power_in"))
      (node (ref "P13") (pin "2") (pinfunction "2_2") (pintype "passive"))
      (node (ref "P13") (pin "4") (pinfunction "4_4") (pintype "passive"))
      (node (ref "P13") (pin "8") (pinfunction "8_8") (pintype "passive"))
      (node (ref "P18") (pin "1") (pinfunction "1_1") (pintype "passive"))
      (node (ref "P20") (pin "2") (pinfunction "2_2") (pintype "passive"))
      (node (ref "P7") (pin "1") (pinfunction "1_1") (pintype "passive"))
      (node (ref "P7") (pin "2") (pinfunction "2_2") (pintype "passive"))
      (node (ref "P7") (pin "4") (pinfunction "4_4") (pintype "power_in"))
      (node (ref "R21") (pin "2") (pinfunction "2_2") (pintype "passive"))
      (node (ref "R22") (pin "2") (pinfunction "2_2") (pintype "passive"))
      (node (ref "R23") (pin "2") (pinfunction "2_2") (pintype "passive"))
      (node (ref "R39") (pin "2") (pinfunction "2_2") (pintype "passive"))
    )
    (net (code "70") (name "unconnected-(J2-ID-Pad4)") (class "Default")
      (node (ref "J2") (pin "4") (pinfunction "ID_4") (pintype "passive"))
    )
    (net (code "71") (name "unconnected-(J3-Pad7)") (class "Default")
      (node (ref "J3") (pin "7") (pinfunction "7_7") (pintype "passive"))
    )
    (net (code "72") (name "unconnected-(J3-Pad9)") (class "Default")
      (node (ref "J3") (pin "9") (pinfunction "9_9") (pintype "passive"))
    )
    (net (code "73") (name "unconnected-(P18-Pad7)") (class "Default")
      (node (ref "P18") (pin "7") (pinfunction "7_7") (pintype "passive"))
    )
    (net (code "74") (name "unconnected-(P18-Pad8)") (class "Default")
      (node (ref "P18") (pin "8") (pinfunction "8_8") (pintype "passive"))
    )
    (net (code "75") (name "unconnected-(P19-Pad7)") (class "Default")
      (node (ref "P19") (pin "7") (pinfunction "7_7") (pintype "passive"))
    )
    (net (code "76") (name "unconnected-(P19-Pad8)") (class "Default")
      (node (ref "P19") (pin "8") (pinfunction "8_8") (pintype "passive"))
    )
  )
)
